# BLE_MCU_Watch_Dog_and_Reset_EEPROM_Buzze.net
KiCad netlist of a schematic drawn in Altium Designer
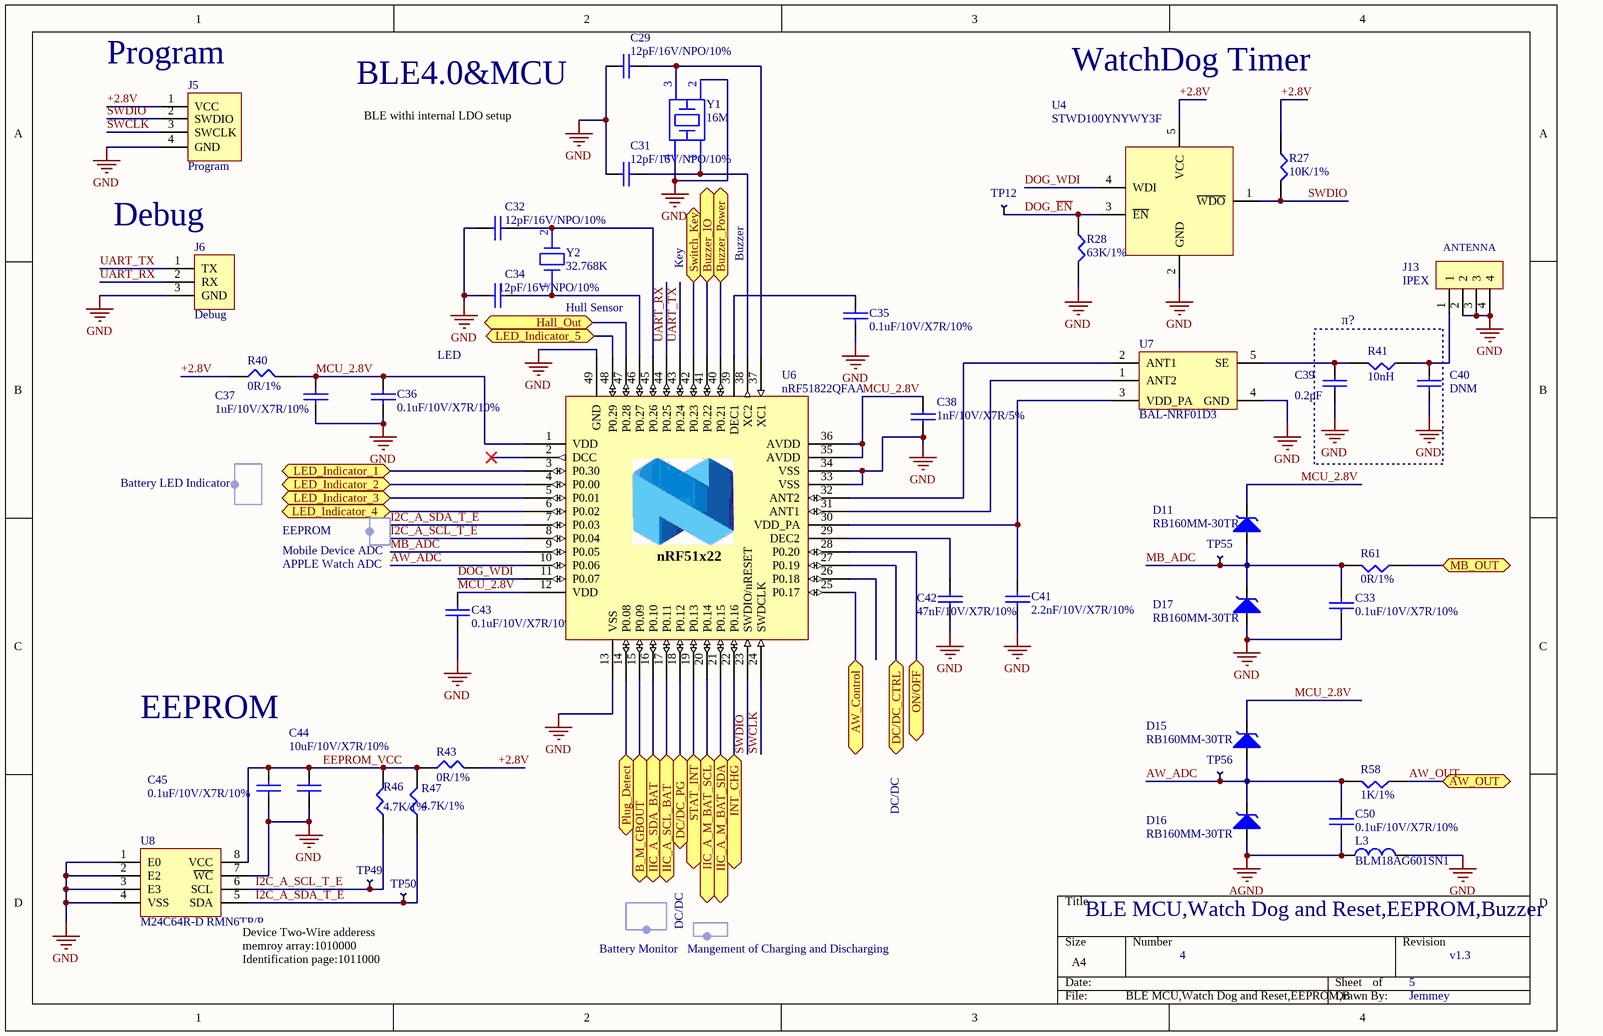
[diagram p0: BLE MCU,Watch Dog and Reset,EEPROM,Buzzer.SchDoc]

(export (version "E")
  (design (tool "Eeschema 10.0.6"))
  (components
    (comp (ref "C29")
      (value "12pF/16V/NPO/10%")
      (footprint "0402C")
      (description "厂家：Murata，型号：GRM1555C1H120JA01D")
      (libsource (lib "Amber") (part "CAP"))
    )
    (comp (ref "C31")
      (value "12pF/16V/NPO/10%")
      (footprint "0402C")
      (description "厂家：Murata，型号：GRM1555C1H120JA01D")
      (libsource (lib "Amber") (part "CAP"))
    )
    (comp (ref "C32")
      (value "12pF/16V/NPO/10%")
      (footprint "0402C")
      (description "厂家：Murata，型号：GRM1555C1H120JA01D")
      (libsource (lib "Amber") (part "CAP"))
    )
    (comp (ref "C33")
      (value "0.1uF/10V/X7R/10%")
      (footprint "0402C")
      (description "厂家：Murata，型号：GRM155R71A104KA01D")
      (libsource (lib "*") (part "CAP"))
    )
    (comp (ref "C34")
      (value "12pF/16V/NPO/10%")
      (footprint "0402C")
      (description "厂家：Murata，型号：GRM1555C1H120JA01D")
      (libsource (lib "Amber") (part "CAP"))
    )
    (comp (ref "C35")
      (value "0.1uF/10V/X7R/10%")
      (footprint "0402C")
      (description "厂家：Murata，型号：GRM155R71A104KA01D")
      (libsource (lib "Amber") (part "CAP"))
    )
    (comp (ref "C36")
      (value "0.1uF/10V/X7R/10%")
      (footprint "0402C")
      (description "厂家：Murata，型号：GRM155R71A104KA01D")
      (libsource (lib "Amber") (part "CAP"))
    )
    (comp (ref "C37")
      (value "1uF/10V/X7R/10%")
      (footprint "0402C")
      (description "厂家：Murata，型号：GRM155R61C105KA12D")
      (libsource (lib "Amber") (part "CAP"))
    )
    (comp (ref "C38")
      (value "1nF/10V/X7R/5%")
      (footprint "0402C")
      (description "厂家：Murata，型号：GRM1555C1H102JA01D")
      (libsource (lib "Amber") (part "CAP"))
    )
    (comp (ref "C39")
      (value "0.2pF")
      (footprint "0402C")
      (description "厂家：Murata，型号：GRM1555C1H1R0BA01D")
      (libsource (lib "*") (part "CAP"))
    )
    (comp (ref "C40")
      (value "DNM")
      (footprint "0402C")
      (description "None")
      (libsource (lib "*") (part "CAP"))
    )
    (comp (ref "C41")
      (value "2.2nF/10V/X7R/10%")
      (footprint "0402C")
      (description "厂家：Murata，型号：GRM155R71H222KA01D")
      (libsource (lib "Amber") (part "CAP"))
    )
    (comp (ref "C42")
      (value "47nF/10V/X7R/10%")
      (footprint "0402C")
      (description "厂家：Murata，型号：GRM155R71H473KE14D")
      (libsource (lib "Amber") (part "CAP"))
    )
    (comp (ref "C43")
      (value "0.1uF/10V/X7R/10%")
      (footprint "0402C")
      (description "厂家：Murata，型号：GRM155R71A104KA01D")
      (libsource (lib "Amber") (part "CAP"))
    )
    (comp (ref "C44")
      (value "10uF/10V/X7R/10%")
      (footprint "0603C")
      (description "厂家：Murata，型号：GRM188R61A106KE69D")
      (libsource (lib "*") (part "CAP"))
    )
    (comp (ref "C45")
      (value "0.1uF/10V/X7R/10%")
      (footprint "0402C")
      (description "厂家：Murata，型号：GRM155R71A104KA01D")
      (libsource (lib "*") (part "CAP"))
    )
    (comp (ref "C50")
      (value "0.1uF/10V/X7R/10%")
      (footprint "0402C")
      (description "厂家：Murata，型号：GRM155R71A104KA01D")
      (libsource (lib "*") (part "CAP"))
    )
    (comp (ref "D11")
      (value "RB160MM-30TR")
      (footprint "DO-214AC")
      (description "厂家：ROHM，型号：RB160MM-30TR")
      (libsource (lib "Moji_Assenbly Test") (part "Schottky barrier rectifier"))
    )
    (comp (ref "D15")
      (value "RB160MM-30TR")
      (footprint "DO-214AC")
      (description "厂家：ROHM，型号：RB160MM-30TR")
      (libsource (lib "Moji_Assenbly Test") (part "Schottky barrier rectifier"))
    )
    (comp (ref "D16")
      (value "RB160MM-30TR")
      (footprint "DO-214AC")
      (description "厂家：ROHM，型号：RB160MM-30TR")
      (libsource (lib "Moji_Assenbly Test") (part "Schottky barrier rectifier"))
    )
    (comp (ref "D17")
      (value "RB160MM-30TR")
      (footprint "DO-214AC")
      (description "厂家：ROHM，型号：RB160MM-30TR")
      (libsource (lib "Moji_Assenbly Test") (part "Schottky barrier rectifier"))
    )
    (comp (ref "J5")
      (value "Program")
      (footprint "PROGRAM - 1.27")
      (description "厂家：暂定，型号：暂定")
      (libsource (lib "Amber") (part "Program"))
    )
    (comp (ref "J6")
      (value "Debug")
      (footprint "Debug- 1.27")
      (description "厂家：暂定，型号：暂定")
      (libsource (lib "Amber") (part "Debug_1"))
    )
    (comp (ref "J13")
      (value "IPEX")
      (footprint "IPEX")
      (description "厂家：Molex，型号：73420110_sd")
      (libsource (lib "Amber") (part "ANTA"))
    )
    (comp (ref "L3")
      (value "BLM18AG601SN1")
      (footprint "0603R")
      (description "厂家：MURATA，型号：BLM18AG601SN1")
      (libsource (lib "Amber") (part "CHOKE"))
    )
    (comp (ref "R27")
      (value "10K/1%")
      (footprint "0402R")
      (description "厂家：Yageo，型号：RC0402FR-0710KL")
      (libsource (lib "*") (part "RES1"))
    )
    (comp (ref "R28")
      (value "63K/1%")
      (footprint "0402R")
      (description "厂家：Yageo，型号：RC0402FR-0763KL")
      (libsource (lib "*") (part "RES1"))
    )
    (comp (ref "R40")
      (value "0R/1%")
      (footprint "0603R")
      (description "厂家：Yageo，型号：RC0402FR-070RL")
      (libsource (lib "*") (part "RES1"))
    )
    (comp (ref "R41")
      (value "10nH")
      (footprint "0402R")
      (description "厂家：Yageo，型号：RC0402FR-070RL")
      (libsource (lib "*") (part "RES1"))
    )
    (comp (ref "R43")
      (value "0R/1%")
      (footprint "0603R")
      (description "厂家：Yageo，型号：RC0402FR-070RL")
      (libsource (lib "*") (part "RES1"))
    )
    (comp (ref "R46")
      (value "4.7K/1%")
      (footprint "0402R")
      (description "厂家：Yageo，型号：RC0402FR-074K7L")
      (libsource (lib "*") (part "RES1"))
    )
    (comp (ref "R47")
      (value "4.7K/1%")
      (footprint "0402R")
      (description "厂家：Yageo，型号：RC0402FR-074K7L")
      (libsource (lib "*") (part "RES1"))
    )
    (comp (ref "R58")
      (value "1K/1%")
      (footprint "0402R")
      (description "厂家：Yageo，型号：RC0402FR-070RL")
      (libsource (lib "*") (part "RES1"))
    )
    (comp (ref "R61")
      (value "0R/1%")
      (footprint "0402R")
      (description "厂家：Yageo，型号：RC0402FR-070RL")
      (libsource (lib "*") (part "RES1"))
    )
    (comp (ref "TP12")
      (value "TEST")
      (footprint "Test Pad")
      (description "Test Point")
      (libsource (lib "Amber") (part "TEST"))
    )
    (comp (ref "TP49")
      (value "TEST")
      (footprint "Test Pad")
      (description "Test Point")
      (libsource (lib "Amber") (part "TEST"))
    )
    (comp (ref "TP50")
      (value "TEST")
      (footprint "Test Pad")
      (description "Test Point")
      (libsource (lib "Amber") (part "TEST"))
    )
    (comp (ref "TP55")
      (value "TEST")
      (footprint "Test Pad")
      (description "Test Point")
      (libsource (lib "Amber") (part "TEST"))
    )
    (comp (ref "TP56")
      (value "TEST")
      (footprint "Test Pad")
      (description "Test Point")
      (libsource (lib "Amber") (part "TEST"))
    )
    (comp (ref "U4")
      (value "STWD100YNYWY3F")
      (description "厂家：ST，型号：STWD100YNYWY3F")
      (libsource (lib "Amber") (part "STWD100"))
    )
    (comp (ref "U6")
      (value "nRF51822QFAA")
      (description "厂家：Nordic，型号：Nrf51822QFAA")
      (libsource (lib "Amber") (part "nRF51822"))
    )
    (comp (ref "U7")
      (value "BAL-NRF01D3")
      (description "厂家：ST，型号：BAL-NRF01D3")
      (libsource (lib "Amber") (part "BAL-NRF01D3"))
    )
    (comp (ref "U8")
      (value "M24C64R-D RMN6TP/P")
      (footprint "SO8N")
      (description "厂家：ST，型号：M24C64R-D RMN6TP/P")
      (libsource (lib "Amber") (part "M24C64-R"))
    )
    (comp (ref "Y1")
      (value "16M")
      (footprint "XTALSMD2-2520")
      (description "厂家：EPSON，型号：Q24FA20H0004400")
      (libsource (lib "Amber_1") (part "CRYSTAL2"))
    )
    (comp (ref "Y2")
      (value "32.768K")
      (footprint "XTALSMD2-3215")
      (description "厂家：EPSON，型号：Q13FC1350000400")
      (libsource (lib "Amber") (part "CRYSTAL3"))
    )
  )
  (nets
    (net (code "1") (name "/+2.8V") (class "Default")
      (node (ref "J5") (pin "1") (pinfunction "VCC_1") (pintype "passive"))
      (node (ref "R27") (pin "1") (pinfunction "1_1") (pintype "passive"))
      (node (ref "R40") (pin "1") (pinfunction "1_1") (pintype "passive"))
      (node (ref "R43") (pin "2") (pinfunction "2_2") (pintype "passive"))
      (node (ref "U4") (pin "5") (pinfunction "VCC_5") (pintype "passive"))
    )
    (net (code "2") (name "/AW_ADC") (class "Default")
      (node (ref "C50") (pin "1") (pinfunction "1_1") (pintype "passive"))
      (node (ref "D15") (pin "2") (pinfunction "A_2") (pintype "passive"))
      (node (ref "D16") (pin "1") (pinfunction "K_1") (pintype "passive"))
      (node (ref "R58") (pin "2") (pinfunction "2_2") (pintype "passive"))
      (node (ref "TP56") (pin "1") (pinfunction "1_1") (pintype "passive"))
      (node (ref "U6") (pin "10") (pinfunction "P0.06_10") (pintype "bidirectional"))
    )
    (net (code "3") (name "/AW_Control") (class "Default")
      (node (ref "U6") (pin "25") (pinfunction "P0.17_25") (pintype "bidirectional"))
    )
    (net (code "4") (name "/AW_OUT") (class "Default")
      (node (ref "R58") (pin "1") (pinfunction "1_1") (pintype "passive"))
    )
    (net (code "5") (name "/B_M_GBOUT") (class "Default")
      (node (ref "U6") (pin "15") (pinfunction "P0.09_15") (pintype "bidirectional"))
    )
    (net (code "6") (name "/Buzzer_IO") (class "Default")
      (node (ref "U6") (pin "41") (pinfunction "P0.22_41") (pintype "bidirectional"))
    )
    (net (code "7") (name "/Buzzer_Power") (class "Default")
      (node (ref "U6") (pin "40") (pinfunction "P0.21_40") (pintype "bidirectional"))
    )
    (net (code "8") (name "/DC{slash}DC_CTRL") (class "Default")
      (node (ref "U6") (pin "27") (pinfunction "P0.19_27") (pintype "bidirectional"))
    )
    (net (code "9") (name "/DC{slash}DC_PG") (class "Default")
      (node (ref "U6") (pin "18") (pinfunction "P0.12_18") (pintype "bidirectional"))
    )
    (net (code "10") (name "/DOG_WDI") (class "Default")
      (node (ref "U4") (pin "4") (pinfunction "WDI_4") (pintype "passive"))
      (node (ref "U6") (pin "11") (pinfunction "P0.07_11") (pintype "bidirectional"))
    )
    (net (code "11") (name "/DOG_~{EN}") (class "Default")
      (node (ref "R28") (pin "1") (pinfunction "1_1") (pintype "passive"))
      (node (ref "TP12") (pin "1") (pinfunction "1_1") (pintype "passive"))
      (node (ref "U4") (pin "3") (pinfunction "~{EN}_3") (pintype "passive"))
    )
    (net (code "12") (name "/EEPROM_VCC") (class "Default")
      (node (ref "C44") (pin "1") (pinfunction "1_1") (pintype "passive"))
      (node (ref "C45") (pin "1") (pinfunction "1_1") (pintype "passive"))
      (node (ref "R43") (pin "1") (pinfunction "1_1") (pintype "passive"))
      (node (ref "R46") (pin "2") (pinfunction "2_2") (pintype "passive"))
      (node (ref "R47") (pin "2") (pinfunction "2_2") (pintype "passive"))
      (node (ref "U8") (pin "8") (pinfunction "VCC_8") (pintype "passive"))
    )
    (net (code "13") (name "/Hall_Out") (class "Default")
      (node (ref "U6") (pin "47") (pinfunction "P0.28_47") (pintype "bidirectional"))
    )
    (net (code "14") (name "/I2C_A_SCL_T_E") (class "Default")
      (node (ref "R46") (pin "1") (pinfunction "1_1") (pintype "passive"))
      (node (ref "TP49") (pin "1") (pinfunction "1_1") (pintype "passive"))
      (node (ref "U6") (pin "8") (pinfunction "P0.04_8") (pintype "bidirectional"))
      (node (ref "U8") (pin "6") (pinfunction "SCL_6") (pintype "passive"))
    )
    (net (code "15") (name "/I2C_A_SDA_T_E") (class "Default")
      (node (ref "R47") (pin "1") (pinfunction "1_1") (pintype "passive"))
      (node (ref "TP50") (pin "1") (pinfunction "1_1") (pintype "passive"))
      (node (ref "U6") (pin "7") (pinfunction "P0.03_7") (pintype "bidirectional"))
      (node (ref "U8") (pin "5") (pinfunction "SDA_5") (pintype "passive"))
    )
    (net (code "16") (name "/IIC_A_M_BAT_SCL") (class "Default")
      (node (ref "U6") (pin "20") (pinfunction "P0.14_20") (pintype "bidirectional"))
    )
    (net (code "17") (name "/IIC_A_M_BAT_SDA") (class "Default")
      (node (ref "U6") (pin "21") (pinfunction "P0.15_21") (pintype "bidirectional"))
    )
    (net (code "18") (name "/IIC_A_SCL_BAT") (class "Default")
      (node (ref "U6") (pin "17") (pinfunction "P0.11_17") (pintype "bidirectional"))
    )
    (net (code "19") (name "/IIC_A_SDA_BAT") (class "Default")
      (node (ref "U6") (pin "16") (pinfunction "P0.10_16") (pintype "bidirectional"))
    )
    (net (code "20") (name "/INT_CHG") (class "Default")
      (node (ref "U6") (pin "22") (pinfunction "P0.16_22") (pintype "bidirectional"))
    )
    (net (code "21") (name "/LED_Indicator_1") (class "Default")
      (node (ref "U6") (pin "3") (pinfunction "P0.30_3") (pintype "bidirectional"))
    )
    (net (code "22") (name "/LED_Indicator_2") (class "Default")
      (node (ref "U6") (pin "4") (pinfunction "P0.00_4") (pintype "bidirectional"))
    )
    (net (code "23") (name "/LED_Indicator_3") (class "Default")
      (node (ref "U6") (pin "5") (pinfunction "P0.01_5") (pintype "bidirectional"))
    )
    (net (code "24") (name "/LED_Indicator_4") (class "Default")
      (node (ref "U6") (pin "6") (pinfunction "P0.02_6") (pintype "bidirectional"))
    )
    (net (code "25") (name "/LED_Indicator_5") (class "Default")
      (node (ref "U6") (pin "48") (pinfunction "P0.29_48") (pintype "bidirectional"))
    )
    (net (code "26") (name "/MB_ADC") (class "Default")
      (node (ref "C33") (pin "1") (pinfunction "1_1") (pintype "passive"))
      (node (ref "D11") (pin "2") (pinfunction "A_2") (pintype "passive"))
      (node (ref "D17") (pin "1") (pinfunction "K_1") (pintype "passive"))
      (node (ref "R61") (pin "2") (pinfunction "2_2") (pintype "passive"))
      (node (ref "TP55") (pin "1") (pinfunction "1_1") (pintype "passive"))
      (node (ref "U6") (pin "9") (pinfunction "P0.05_9") (pintype "bidirectional"))
    )
    (net (code "27") (name "/MB_OUT") (class "Default")
      (node (ref "R61") (pin "1") (pinfunction "1_1") (pintype "passive"))
    )
    (net (code "28") (name "/MCU_2.8V") (class "Default")
      (node (ref "C36") (pin "2") (pinfunction "2_2") (pintype "passive"))
      (node (ref "C37") (pin "2") (pinfunction "2_2") (pintype "passive"))
      (node (ref "C38") (pin "2") (pinfunction "2_2") (pintype "passive"))
      (node (ref "C43") (pin "2") (pinfunction "2_2") (pintype "passive"))
      (node (ref "D11") (pin "1") (pinfunction "K_1") (pintype "passive"))
      (node (ref "D15") (pin "1") (pinfunction "K_1") (pintype "passive"))
      (node (ref "R40") (pin "2") (pinfunction "2_2") (pintype "passive"))
      (node (ref "U6") (pin "1") (pinfunction "VDD_1") (pintype "power_in"))
      (node (ref "U6") (pin "12") (pinfunction "VDD_12") (pintype "power_in"))
      (node (ref "U6") (pin "35") (pinfunction "AVDD_35") (pintype "power_in"))
      (node (ref "U6") (pin "36") (pinfunction "AVDD_36") (pintype "power_in"))
    )
    (net (code "29") (name "/ON{slash}OFF") (class "Default")
      (node (ref "U6") (pin "28") (pinfunction "P0.20_28") (pintype "bidirectional"))
    )
    (net (code "30") (name "/Plug_Detect") (class "Default")
      (node (ref "U6") (pin "14") (pinfunction "P0.08_14") (pintype "bidirectional"))
    )
    (net (code "31") (name "/STAT_INT") (class "Default")
      (node (ref "U6") (pin "19") (pinfunction "P0.13_19") (pintype "bidirectional"))
    )
    (net (code "32") (name "/SWCLK") (class "Default")
      (node (ref "J5") (pin "3") (pinfunction "SWCLK_3") (pintype "passive"))
      (node (ref "U6") (pin "24") (pinfunction "SWDCLK_24") (pintype "input"))
    )
    (net (code "33") (name "/SWDIO") (class "Default")
      (node (ref "J5") (pin "2") (pinfunction "SWDIO_2") (pintype "passive"))
      (node (ref "R27") (pin "2") (pinfunction "2_2") (pintype "passive"))
      (node (ref "U4") (pin "1") (pinfunction "~{WDO}_1") (pintype "passive"))
      (node (ref "U6") (pin "23") (pinfunction "SWDIO/nRESET_23") (pintype "input"))
    )
    (net (code "34") (name "/Switch_Key") (class "Default")
      (node (ref "U6") (pin "42") (pinfunction "P0.23_42") (pintype "bidirectional"))
    )
    (net (code "35") (name "/UART_RX") (class "Default")
      (node (ref "J6") (pin "2") (pinfunction "RX_2") (pintype "passive"))
      (node (ref "U6") (pin "44") (pinfunction "P0.25_44") (pintype "bidirectional"))
    )
    (net (code "36") (name "/UART_TX") (class "Default")
      (node (ref "J6") (pin "1") (pinfunction "TX_1") (pintype "passive"))
      (node (ref "U6") (pin "43") (pinfunction "P0.24_43") (pintype "bidirectional"))
    )
    (net (code "37") (name "AGND") (class "Default")
      (node (ref "C50") (pin "2") (pinfunction "2_2") (pintype "passive"))
      (node (ref "D16") (pin "2") (pinfunction "A_2") (pintype "passive"))
      (node (ref "L3") (pin "1") (pinfunction "1_1") (pintype "passive"))
    )
    (net (code "38") (name "GND") (class "Default")
      (node (ref "C29") (pin "1") (pinfunction "1_1") (pintype "passive"))
      (node (ref "C31") (pin "1") (pinfunction "1_1") (pintype "passive"))
      (node (ref "C32") (pin "1") (pinfunction "1_1") (pintype "passive"))
      (node (ref "C33") (pin "2") (pinfunction "2_2") (pintype "passive"))
      (node (ref "C34") (pin "1") (pinfunction "1_1") (pintype "passive"))
      (node (ref "C35") (pin "1") (pinfunction "1_1") (pintype "passive"))
      (node (ref "C36") (pin "1") (pinfunction "1_1") (pintype "passive"))
      (node (ref "C37") (pin "1") (pinfunction "1_1") (pintype "passive"))
      (node (ref "C38") (pin "1") (pinfunction "1_1") (pintype "passive"))
      (node (ref "C39") (pin "2") (pinfunction "2_2") (pintype "passive"))
      (node (ref "C40") (pin "2") (pinfunction "2_2") (pintype "passive"))
      (node (ref "C41") (pin "1") (pinfunction "1_1") (pintype "passive"))
      (node (ref "C42") (pin "1") (pinfunction "1_1") (pintype "passive"))
      (node (ref "C43") (pin "1") (pinfunction "1_1") (pintype "passive"))
      (node (ref "C44") (pin "2") (pinfunction "2_2") (pintype "passive"))
      (node (ref "C45") (pin "2") (pinfunction "2_2") (pintype "passive"))
      (node (ref "D17") (pin "2") (pinfunction "A_2") (pintype "passive"))
      (node (ref "J13") (pin "2") (pinfunction "2_2") (pintype "passive"))
      (node (ref "J13") (pin "3") (pinfunction "3_3") (pintype "passive"))
      (node (ref "J13") (pin "4") (pinfunction "4_4") (pintype "passive"))
      (node (ref "J5") (pin "4") (pinfunction "GND_4") (pintype "passive"))
      (node (ref "J6") (pin "3") (pinfunction "GND_3") (pintype "passive"))
      (node (ref "L3") (pin "2") (pinfunction "2_2") (pintype "passive"))
      (node (ref "R28") (pin "2") (pinfunction "2_2") (pintype "passive"))
      (node (ref "U4") (pin "2") (pinfunction "GND_2") (pintype "passive"))
      (node (ref "U6") (pin "13") (pinfunction "VSS_13") (pintype "power_in"))
      (node (ref "U6") (pin "33") (pinfunction "VSS_33") (pintype "power_in"))
      (node (ref "U6") (pin "34") (pinfunction "VSS_34") (pintype "power_in"))
      (node (ref "U6") (pin "49") (pinfunction "GND_49") (pintype "power_in"))
      (node (ref "U7") (pin "4") (pinfunction "GND_4") (pintype "passive"))
      (node (ref "U8") (pin "1") (pinfunction "E0_1") (pintype "passive"))
      (node (ref "U8") (pin "2") (pinfunction "E2_2") (pintype "passive"))
      (node (ref "U8") (pin "3") (pinfunction "E3_3") (pintype "passive"))
      (node (ref "U8") (pin "4") (pinfunction "VSS_4") (pintype "passive"))
      (node (ref "U8") (pin "7") (pinfunction "~{WC}_7") (pintype "passive"))
      (node (ref "Y1") (pin "2") (pinfunction "2_2") (pintype "passive"))
      (node (ref "Y1") (pin "4") (pinfunction "4_4") (pintype "passive"))
    )
    (net (code "39") (name "Net-(C40-Pad1)") (class "Default")
      (node (ref "C40") (pin "1") (pinfunction "1_1") (pintype "passive"))
      (node (ref "J13") (pin "1") (pinfunction "1_1") (pintype "passive"))
      (node (ref "R41") (pin "1") (pinfunction "1_1") (pintype "passive"))
    )
    (net (code "40") (name "Net-(U6-ANT1)") (class "Default")
      (node (ref "U6") (pin "31") (pinfunction "ANT1_31") (pintype "bidirectional"))
      (node (ref "U7") (pin "1") (pinfunction "ANT2_1") (pintype "passive"))
    )
    (net (code "41") (name "Net-(U6-ANT2)") (class "Default")
      (node (ref "U6") (pin "32") (pinfunction "ANT2_32") (pintype "bidirectional"))
      (node (ref "U7") (pin "2") (pinfunction "ANT1_2") (pintype "passive"))
    )
    (net (code "42") (name "Net-(U6-DEC1)") (class "Default")
      (node (ref "C35") (pin "2") (pinfunction "2_2") (pintype "passive"))
      (node (ref "U6") (pin "39") (pinfunction "DEC1_39") (pintype "power_in"))
    )
    (net (code "43") (name "Net-(U6-DEC2)") (class "Default")
      (node (ref "C42") (pin "2") (pinfunction "2_2") (pintype "passive"))
      (node (ref "U6") (pin "29") (pinfunction "DEC2_29") (pintype "power_in"))
    )
    (net (code "44") (name "Net-(U6-P0.26)") (class "Default")
      (node (ref "C32") (pin "2") (pinfunction "2_2") (pintype "passive"))
      (node (ref "U6") (pin "45") (pinfunction "P0.26_45") (pintype "bidirectional"))
      (node (ref "Y2") (pin "2") (pinfunction "2_2") (pintype "passive"))
    )
    (net (code "45") (name "Net-(U6-P0.27)") (class "Default")
      (node (ref "C34") (pin "2") (pinfunction "2_2") (pintype "passive"))
      (node (ref "U6") (pin "46") (pinfunction "P0.27_46") (pintype "bidirectional"))
      (node (ref "Y2") (pin "1") (pinfunction "1_1") (pintype "passive"))
    )
    (net (code "46") (name "Net-(U6-VDD_PA)") (class "Default")
      (node (ref "C41") (pin "2") (pinfunction "2_2") (pintype "passive"))
      (node (ref "U6") (pin "30") (pinfunction "VDD_PA_30") (pintype "power_in"))
      (node (ref "U7") (pin "3") (pinfunction "VDD_PA_3") (pintype "passive"))
    )
    (net (code "47") (name "Net-(U6-XC1)") (class "Default")
      (node (ref "C29") (pin "2") (pinfunction "2_2") (pintype "passive"))
      (node (ref "U6") (pin "37") (pinfunction "XC1_37") (pintype "input"))
      (node (ref "Y1") (pin "3") (pinfunction "3_3") (pintype "passive"))
    )
    (net (code "48") (name "Net-(U6-XC2)") (class "Default")
      (node (ref "C31") (pin "2") (pinfunction "2_2") (pintype "passive"))
      (node (ref "U6") (pin "38") (pinfunction "XC2_38") (pintype "output"))
      (node (ref "Y1") (pin "1") (pinfunction "1_1") (pintype "passive"))
    )
    (net (code "49") (name "Net-(U7-SE)") (class "Default")
      (node (ref "C39") (pin "1") (pinfunction "1_1") (pintype "passive"))
      (node (ref "R41") (pin "2") (pinfunction "2_2") (pintype "passive"))
      (node (ref "U7") (pin "5") (pinfunction "SE_5") (pintype "passive"))
    )
    (net (code "50") (name "unconnected-(U6-DCC-Pad2)") (class "Default")
      (node (ref "U6") (pin "2") (pinfunction "DCC_2") (pintype "output+no_connect"))
    )
    (net (code "51") (name "unconnected-(U6-P0.18-Pad26)") (class "Default")
      (node (ref "U6") (pin "26") (pinfunction "P0.18_26") (pintype "bidirectional"))
    )
  )
)
